# H03R0-T.net
KiCad netlist of a schematic drawn in EAGLE
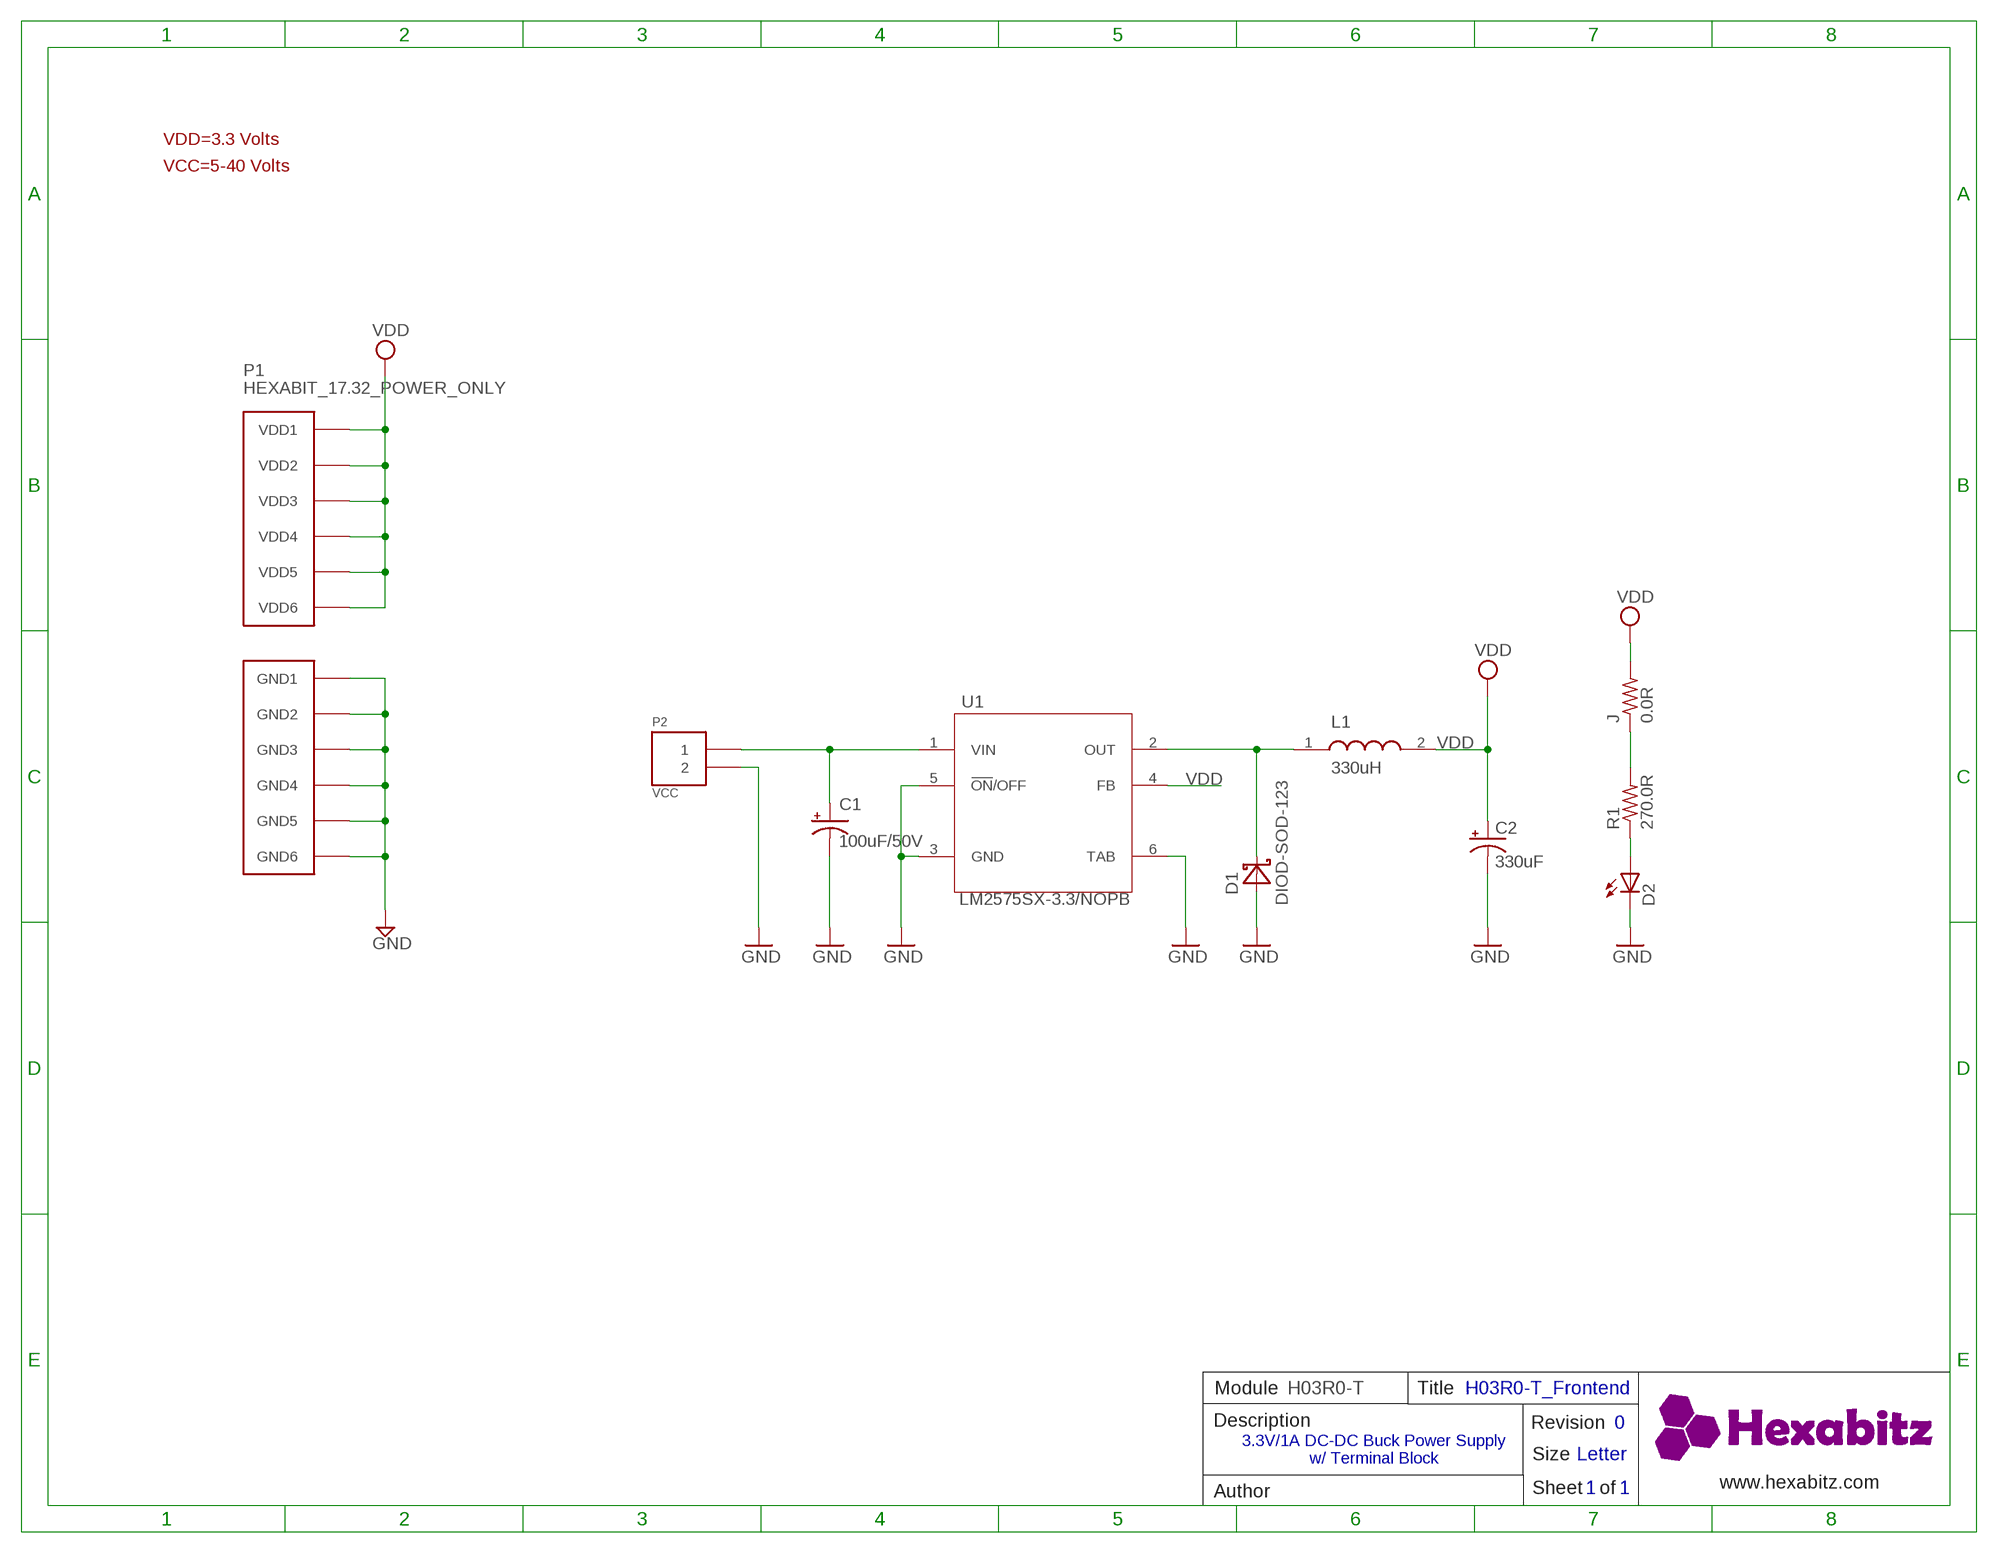
[diagram p0: schematic, sheet 1]

(export (version "E")
  (design (tool "Eeschema 10.0.6"))
  (components
    (comp (ref "C1")
      (value "100uF/50V")
      (footprint "eagle-import:E3,5-8")
      (fields
        (field (name "CAPACITANCE") "100F")
        (field (name "CPACITANCE_RATING") "±20%")
        (field (name "MFN") "Nichicon")
        (field (name "MPN") "UVR1H101MPD1TD")
        (field (name "OCTOPART_ID") "913e58b97f3b4ef9")
        (field (name "OCTOPART_URL") "http://octopart.com/uvr1h101mpd1td-nichicon-9292643")
        (field (name "VOLTAGE_RATING_DC") "50.0 V")
      )
      (libsource (lib "eagle-import") (part "CPOL-US"))
    )
    (comp (ref "C2")
      (value "330uF")
      (footprint "eagle-import:CAPPM7343X200N")
      (fields
        (field (name "MANUFACTURER_PART_NUMBER") "6TPC330MA")
        (field (name "MOUSER_PART_NUMBER") "667-6TPC330MA")
        (field (name "RS_PART_NUMBER") "1666900")
      )
      (libsource (lib "eagle-import") (part "AVX-E"))
    )
    (comp (ref "D1")
      (value "DIOD-SOD-123")
      (footprint "eagle-import:SOD123")
      (fields
        (field (name "CAPACITANCE") "1.1e-10 F")
        (field (name "CURRENT_RATING") "1.0 A")
        (field (name "MFN") "diodes")
        (field (name "MPN") "1N5819HW-7-F")
        (field (name "OCTOPART_ID") "e83e2130232537f9")
        (field (name "OCTOPART_URL") "https://octopart.com/1n5819hw-7-f-diodes+inc.-323197")
        (field (name "VOLTAGE_RATING_DC") "40.0 V")
      )
      (libsource (lib "eagle-import") (part "DIOD-SOD-123"))
    )
    (comp (ref "D2")
      (value "VLMS1300-GS08")
      (footprint "eagle-import:VLMS1300-GS08")
      (fields
        (field (name "MFN") "Vishay")
        (field (name "MPN") "VLMTG1300-GS08")
        (field (name "OCTOPART_URL") "http://octopart.com/vlmtg1300-gs08-vishay-21709202")
      )
      (libsource (lib "eagle-import") (part "VLMS1300-GS08"))
    )
    (comp (ref "J")
      (value "0.0R")
      (footprint "eagle-import:R-0603")
      (fields
        (field (name "MFN") "Yageo")
        (field (name "MPN") "RC0603JR-070RL")
        (field (name "OCTOPART_URL") "https://octopart.com/crcw06030000z0eahp-vishay-44320230")
        (field (name "RESISTANCE") "0.0 Ω")
      )
      (libsource (lib "eagle-import") (part "R-0603"))
    )
    (comp (ref "L1")
      (value "330uH")
      (footprint "eagle-import:SRR1280-150M")
      (fields
        (field (name "MANUFACTURER_PART_NUMBER") "SRR1280-331K")
        (field (name "MOUSER_PART_NUMBER") "652-SRR1280-331K")
        (field (name "RS_PART_NUMBER") "1728540")
      )
      (libsource (lib "eagle-import") (part "SRR1280-331K"))
    )
    (comp (ref "P1")
      (value "HEXABIT_17.32_POWER_ONLY")
      (footprint "eagle-import:HEXABIT_17.32_POWER_ONLY")
      (libsource (lib "eagle-import") (part "HEXABIT_?_POWER_ONLY17.32"))
    )
    (comp (ref "P2")
      (value "VCC")
      (footprint "eagle-import:1546111-2")
      (fields (field (name "MPN") "1546111-2"))
      (libsource (lib "eagle-import") (part "1546111-2"))
    )
    (comp (ref "R1")
      (value "270.0R")
      (footprint "eagle-import:R-0603")
      (fields
        (field (name "MFN") "Yageo")
        (field (name "MPN") "RC0603FR-07270RL")
        (field (name "OCTOPART_URL") "https://octopart.com/crcw0603270rjnea-vishay-39784736")
        (field (name "RESISTANCE") "270.0 Ω")
        (field (name "TOLERANCE") "±5%")
      )
      (libsource (lib "eagle-import") (part "R-0603"))
    )
    (comp (ref "U1")
      (value "LM2575SX-3.3/NOPB")
      (footprint "eagle-import:TO170P1435X457-6N")
      (fields
        (field (name "DIGI-KEY_PART_NUMBER") "LM2575SX-3.3/NOPBCT-ND")
        (field (name "MF") "Texas Instruments")
      )
      (libsource (lib "eagle-import") (part "LM2575SX-3.3/NOPB"))
    )
  )
  (nets
    (net (code "1") (name "GND") (class "Default")
      (node (ref "C1") (pin "-") (pinfunction "-_-") (pintype "passive"))
      (node (ref "C2") (pin "2") (pinfunction "-_2") (pintype "passive"))
      (node (ref "D1") (pin "1") (pinfunction "A_1") (pintype "passive"))
      (node (ref "D2") (pin "C") (pinfunction "C_C") (pintype "passive"))
      (node (ref "P1") (pin "PAD_PD10") (pinfunction "GND4_PAD_PD10") (pintype "power_in"))
      (node (ref "P1") (pin "PAD_PD11") (pinfunction "GND5_PAD_PD11") (pintype "power_in"))
      (node (ref "P1") (pin "PAD_PD12") (pinfunction "GND6_PAD_PD12") (pintype "power_in"))
      (node (ref "P1") (pin "PAD_PD7") (pinfunction "GND1_PAD_PD7") (pintype "power_in"))
      (node (ref "P1") (pin "PAD_PD8") (pinfunction "GND2_PAD_PD8") (pintype "power_in"))
      (node (ref "P1") (pin "PAD_PD9") (pinfunction "GND3_PAD_PD9") (pintype "power_in"))
      (node (ref "P2") (pin "2") (pinfunction "2_2") (pintype "power_in"))
      (node (ref "U1") (pin "3") (pinfunction "GND_3") (pintype "passive"))
      (node (ref "U1") (pin "5") (pinfunction "ON/OFF_5") (pintype "input"))
      (node (ref "U1") (pin "6") (pinfunction "TAB_6") (pintype "passive"))
    )
    (net (code "2") (name "Net-(D1-C)") (class "Default")
      (node (ref "D1") (pin "2") (pinfunction "C_2") (pintype "passive"))
      (node (ref "L1") (pin "1") (pinfunction "1_1") (pintype "bidirectional"))
      (node (ref "U1") (pin "2") (pinfunction "OUT_2") (pintype "output"))
    )
    (net (code "3") (name "Net-(D2-PadA)") (class "Default")
      (node (ref "D2") (pin "A") (pinfunction "A_A") (pintype "passive"))
      (node (ref "R1") (pin "1") (pinfunction "1_1") (pintype "passive"))
    )
    (net (code "4") (name "Net-(J-Pad1)") (class "Default")
      (node (ref "J") (pin "1") (pinfunction "1_1") (pintype "passive"))
      (node (ref "R1") (pin "2") (pinfunction "2_2") (pintype "passive"))
    )
    (net (code "5") (name "Net-(U1-VIN)") (class "Default")
      (node (ref "C1") (pin "+") (pinfunction "+_+") (pintype "passive"))
      (node (ref "P2") (pin "1") (pinfunction "1_1") (pintype "power_in"))
      (node (ref "U1") (pin "1") (pinfunction "VIN_1") (pintype "power_in"))
    )
    (net (code "6") (name "VDD") (class "Default")
      (node (ref "C2") (pin "1") (pinfunction "+_1") (pintype "passive"))
      (node (ref "J") (pin "2") (pinfunction "2_2") (pintype "passive"))
      (node (ref "L1") (pin "2") (pinfunction "2_2") (pintype "bidirectional"))
      (node (ref "P1") (pin "PAD_PU10") (pinfunction "VDD4_PAD_PU10") (pintype "power_in"))
      (node (ref "P1") (pin "PAD_PU11") (pinfunction "VDD5_PAD_PU11") (pintype "power_in"))
      (node (ref "P1") (pin "PAD_PU12") (pinfunction "VDD6_PAD_PU12") (pintype "power_in"))
      (node (ref "P1") (pin "PAD_PU7") (pinfunction "VDD1_PAD_PU7") (pintype "power_in"))
      (node (ref "P1") (pin "PAD_PU8") (pinfunction "VDD2_PAD_PU8") (pintype "power_in"))
      (node (ref "P1") (pin "PAD_PU9") (pinfunction "VDD3_PAD_PU9") (pintype "power_in"))
      (node (ref "U1") (pin "4") (pinfunction "FB_4") (pintype "input"))
    )
  )
)
